# pi433_r02.net
KiCad netlist of a schematic drawn in EAGLE
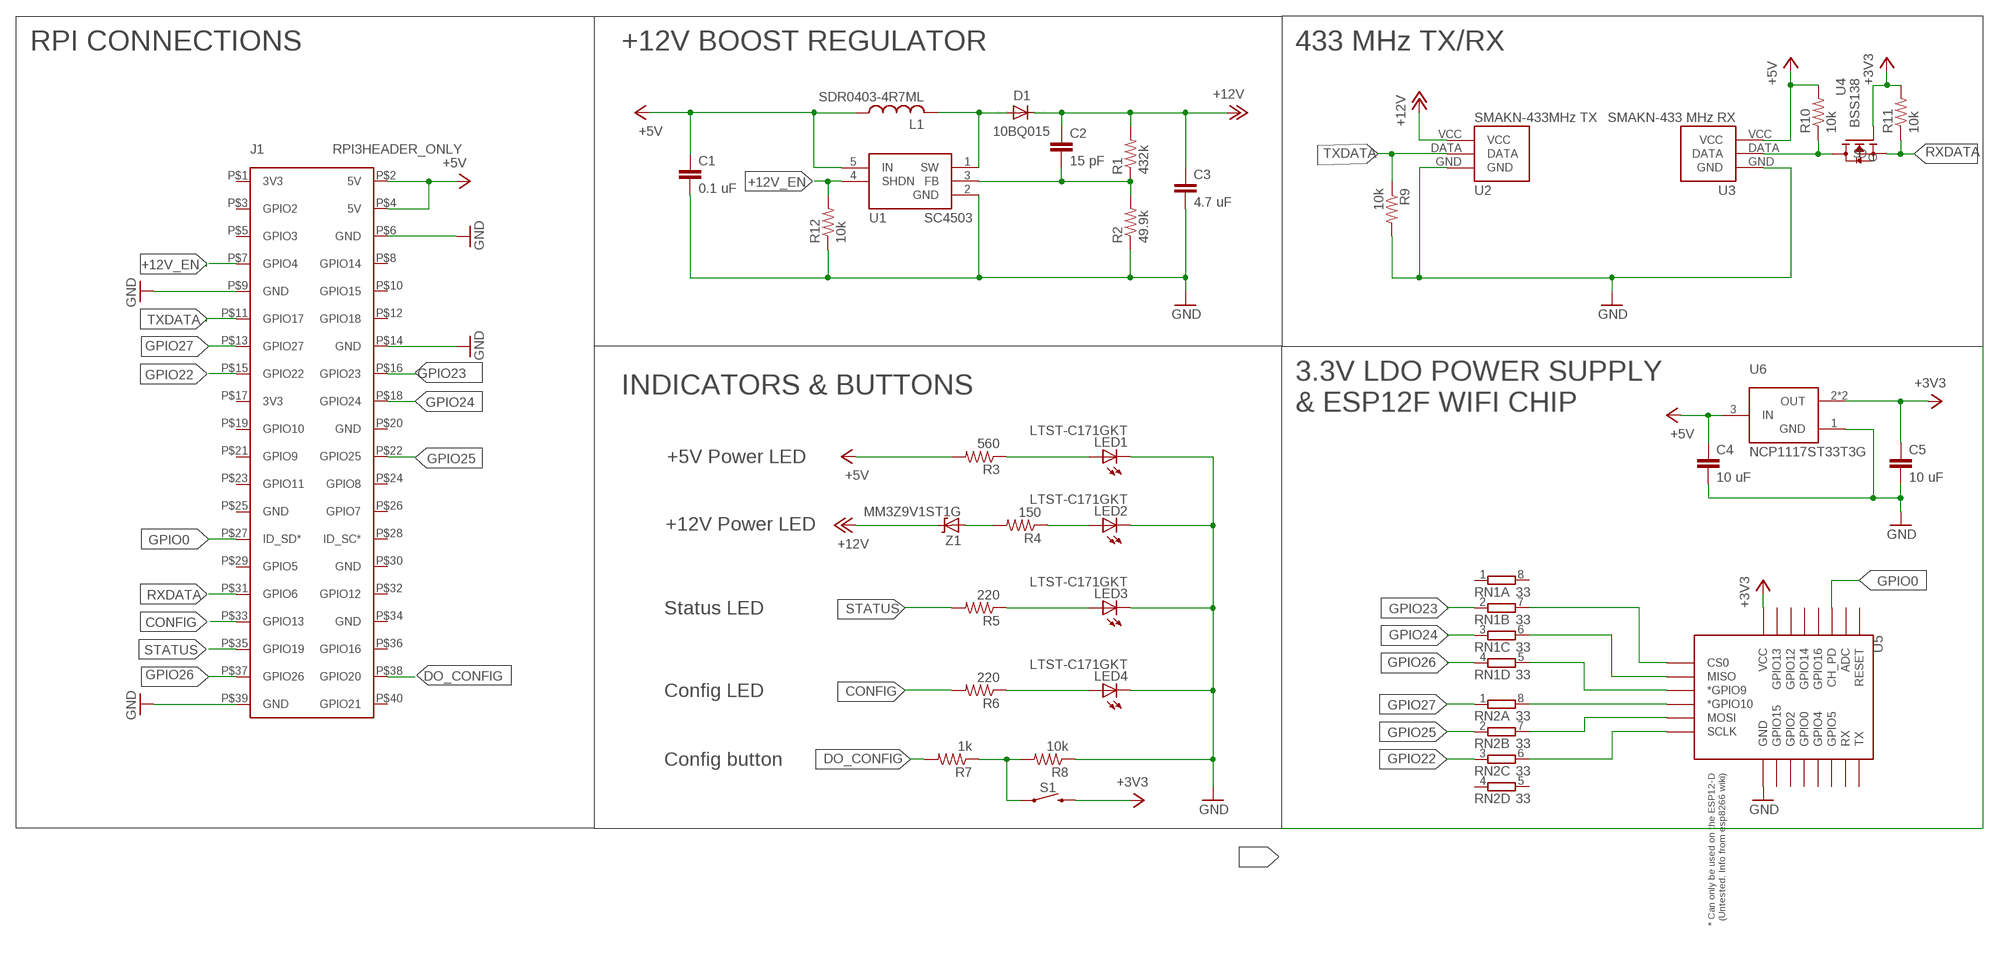
[diagram p0: schematic, sheet 1]

(export (version "E")
  (design (tool "Eeschema 10.0.6"))
  (components
    (comp (ref "C1")
      (value "0.1 uF")
      (footprint "eagle-import:C0603")
      (libsource (lib "eagle-import") (part "C-EUC0603"))
    )
    (comp (ref "C2")
      (value "15 pF")
      (footprint "eagle-import:C0603")
      (libsource (lib "eagle-import") (part "C-EUC0603"))
    )
    (comp (ref "C3")
      (value "4.7 uF")
      (footprint "eagle-import:C0805")
      (libsource (lib "eagle-import") (part "C-EUC0805"))
    )
    (comp (ref "C4")
      (value "10 uF")
      (footprint "eagle-import:C0805")
      (libsource (lib "eagle-import") (part "C-EUC0805"))
    )
    (comp (ref "C5")
      (value "10 uF")
      (footprint "eagle-import:C0805")
      (libsource (lib "eagle-import") (part "C-EUC0805"))
    )
    (comp (ref "D1")
      (value "10BQ015")
      (footprint "eagle-import:DO214AA")
      (libsource (lib "eagle-import") (part "DIODE-DO214AA"))
    )
    (comp (ref "J1")
      (value "RPI3HEADER_ONLY")
      (footprint "eagle-import:RPI3-HEADER_ONLY")
      (libsource (lib "eagle-import") (part "RPI3HEADER_ONLY"))
    )
    (comp (ref "L1")
      (value "SDR0403-4R7ML")
      (footprint "eagle-import:SDR0403")
      (libsource (lib "eagle-import") (part "SDR0403-4R7ML"))
    )
    (comp (ref "LED1")
      (value "LTST-C171GKT")
      (footprint "eagle-import:CHIPLED_0805")
      (libsource (lib "eagle-import") (part "LEDCHIPLED_0805"))
    )
    (comp (ref "LED2")
      (value "LTST-C171GKT")
      (footprint "eagle-import:CHIPLED_0805")
      (libsource (lib "eagle-import") (part "LEDCHIPLED_0805"))
    )
    (comp (ref "LED3")
      (value "LTST-C171GKT")
      (footprint "eagle-import:CHIPLED_0805")
      (libsource (lib "eagle-import") (part "LEDCHIPLED_0805"))
    )
    (comp (ref "LED4")
      (value "LTST-C171GKT")
      (footprint "eagle-import:CHIPLED_0805")
      (libsource (lib "eagle-import") (part "LEDCHIPLED_0805"))
    )
    (comp (ref "R1")
      (value "432k")
      (footprint "eagle-import:R0805")
      (libsource (lib "eagle-import") (part "R-US_R0805"))
    )
    (comp (ref "R2")
      (value "49.9k")
      (footprint "eagle-import:R0805")
      (libsource (lib "eagle-import") (part "R-US_R0805"))
    )
    (comp (ref "R3")
      (value "560")
      (footprint "eagle-import:R0805")
      (libsource (lib "eagle-import") (part "R-US_R0805"))
    )
    (comp (ref "R4")
      (value "150")
      (footprint "eagle-import:R0805")
      (libsource (lib "eagle-import") (part "R-US_R0805"))
    )
    (comp (ref "R5")
      (value "220")
      (footprint "eagle-import:R0805")
      (libsource (lib "eagle-import") (part "R-US_R0805"))
    )
    (comp (ref "R6")
      (value "220")
      (footprint "eagle-import:R0805")
      (libsource (lib "eagle-import") (part "R-US_R0805"))
    )
    (comp (ref "R7")
      (value "1k")
      (footprint "eagle-import:R0805")
      (libsource (lib "eagle-import") (part "R-US_R0805"))
    )
    (comp (ref "R8")
      (value "10k")
      (footprint "eagle-import:R0805")
      (libsource (lib "eagle-import") (part "R-US_R0805"))
    )
    (comp (ref "R9")
      (value "10k")
      (footprint "eagle-import:R0805")
      (libsource (lib "eagle-import") (part "R-US_R0805"))
    )
    (comp (ref "R10")
      (value "10k")
      (footprint "eagle-import:R0805")
      (libsource (lib "eagle-import") (part "R-US_R0805"))
    )
    (comp (ref "R11")
      (value "10k")
      (footprint "eagle-import:R0805")
      (libsource (lib "eagle-import") (part "R-US_R0805"))
    )
    (comp (ref "R12")
      (value "10k")
      (footprint "eagle-import:R0805")
      (libsource (lib "eagle-import") (part "R-US_R0805"))
    )
    (comp (ref "RN1")
      (value "33")
      (footprint "eagle-import:CAY16")
      (libsource (lib "eagle-import") (part "4R-NCAY16"))
    )
    (comp (ref "RN2")
      (value "33")
      (footprint "eagle-import:CAY16")
      (libsource (lib "eagle-import") (part "4R-NCAY16"))
    )
    (comp (ref "S1")
      (value "MOMENTARY-SWITCH-SPST-SMD-6.0X3.5MM")
      (footprint "eagle-import:TACTILE_SWITCH_SMD_6.0X3.5MM")
      (libsource (lib "eagle-import") (part "MOMENTARY-SWITCH-SPST-SMD-6.0X3.5MM"))
    )
    (comp (ref "U1")
      (value "SC4503")
      (footprint "eagle-import:TSOT-23-5")
      (libsource (lib "eagle-import") (part "SC4503"))
    )
    (comp (ref "U2")
      (value "SMAKN-433TX")
      (footprint "eagle-import:SMAKN-433TX")
      (libsource (lib "eagle-import") (part "SMAKN-433TX"))
    )
    (comp (ref "U3")
      (value "SMAKN-433RX")
      (footprint "eagle-import:SMAKN-433RX")
      (libsource (lib "eagle-import") (part "SMAKN-433RX"))
    )
    (comp (ref "U4")
      (value "BSS138")
      (footprint "eagle-import:BSS138")
      (fields (field (name "MF") "Fairchild Semiconductor"))
      (libsource (lib "eagle-import") (part "BSS138"))
    )
    (comp (ref "U5")
      (value "ESP12ESMD")
      (footprint "eagle-import:ESP12E-SMD")
      (libsource (lib "eagle-import") (part "ESP12ESMD"))
    )
    (comp (ref "U6")
      (value "NCP1117ST33T3G")
      (footprint "eagle-import:SOT230P700X180-4N")
      (fields (field (name "MF") "ON Semiconductor"))
      (libsource (lib "eagle-import") (part "NCP1117ST33T3G"))
    )
    (comp (ref "Z1")
      (value "MM3Z9V1ST1G")
      (footprint "eagle-import:ZENER-SOD323")
      (libsource (lib "eagle-import") (part "MM3Z9V1ST1G"))
    )
  )
  (nets
    (net (code "1") (name "+3V3") (class "Default")
      (node (ref "C5") (pin "1") (pinfunction "1_1") (pintype "passive"))
      (node (ref "R11") (pin "2") (pinfunction "2_2") (pintype "passive"))
      (node (ref "S1") (pin "2") (pinfunction "2_2") (pintype "passive"))
      (node (ref "U4") (pin "G") (pinfunction "G_G") (pintype "passive"))
      (node (ref "U5") (pin "VCC") (pinfunction "VCC_VCC") (pintype "bidirectional"))
      (node (ref "U6") (pin "2") (pinfunction "OUT_2") (pintype "output"))
      (node (ref "U6") (pin "4") (pinfunction "OUT_4") (pintype "output"))
    )
    (net (code "2") (name "+5V") (class "Default")
      (node (ref "C1") (pin "1") (pinfunction "1_1") (pintype "passive"))
      (node (ref "C4") (pin "1") (pinfunction "1_1") (pintype "passive"))
      (node (ref "J1") (pin "P$2") (pinfunction "5V_P$2") (pintype "bidirectional"))
      (node (ref "J1") (pin "P$4") (pinfunction "5V_P$4") (pintype "bidirectional"))
      (node (ref "L1") (pin "P$1") (pinfunction "1_P$1") (pintype "passive"))
      (node (ref "R10") (pin "2") (pinfunction "2_2") (pintype "passive"))
      (node (ref "R3") (pin "2") (pinfunction "2_2") (pintype "passive"))
      (node (ref "U1") (pin "5") (pinfunction "IN_5") (pintype "power_in"))
      (node (ref "U3") (pin "VCC") (pinfunction "VCC_VCC") (pintype "bidirectional"))
      (node (ref "U6") (pin "3") (pinfunction "IN_3") (pintype "input"))
    )
    (net (code "3") (name "+12V") (class "Default")
      (node (ref "C2") (pin "1") (pinfunction "1_1") (pintype "passive"))
      (node (ref "C3") (pin "1") (pinfunction "1_1") (pintype "passive"))
      (node (ref "D1") (pin "C") (pinfunction "C_C") (pintype "passive"))
      (node (ref "R1") (pin "2") (pinfunction "2_2") (pintype "passive"))
      (node (ref "U2") (pin "VCC") (pinfunction "VCC_VCC") (pintype "bidirectional"))
      (node (ref "Z1") (pin "C") (pinfunction "C_C") (pintype "passive"))
    )
    (net (code "4") (name "/+12V_EN") (class "Default")
      (node (ref "J1") (pin "P$7") (pinfunction "GPIO4_P$7") (pintype "bidirectional"))
      (node (ref "R12") (pin "2") (pinfunction "2_2") (pintype "passive"))
      (node (ref "U1") (pin "4") (pinfunction "SHDN_4") (pintype "input"))
    )
    (net (code "5") (name "/CONFIG") (class "Default")
      (node (ref "J1") (pin "P$33") (pinfunction "GPIO13_P$33") (pintype "bidirectional"))
      (node (ref "R6") (pin "2") (pinfunction "2_2") (pintype "passive"))
    )
    (net (code "6") (name "/DO_CONFIG") (class "Default")
      (node (ref "J1") (pin "P$38") (pinfunction "GPIO20_P$38") (pintype "bidirectional"))
      (node (ref "R7") (pin "2") (pinfunction "2_2") (pintype "passive"))
    )
    (net (code "7") (name "/GPIO0") (class "Default")
      (node (ref "J1") (pin "P$27") (pinfunction "ID_SD*_P$27") (pintype "bidirectional"))
      (node (ref "U5") (pin "CH_PD") (pinfunction "CH_PD_CH_PD") (pintype "bidirectional"))
    )
    (net (code "8") (name "/GPIO22") (class "Default")
      (node (ref "J1") (pin "P$15") (pinfunction "GPIO22_P$15") (pintype "bidirectional"))
      (node (ref "RN2") (pin "3") (pinfunction "1_3") (pintype "passive"))
    )
    (net (code "9") (name "/GPIO23") (class "Default")
      (node (ref "J1") (pin "P$16") (pinfunction "GPIO23_P$16") (pintype "bidirectional"))
      (node (ref "RN1") (pin "2") (pinfunction "1_2") (pintype "passive"))
    )
    (net (code "10") (name "/GPIO24") (class "Default")
      (node (ref "J1") (pin "P$18") (pinfunction "GPIO24_P$18") (pintype "bidirectional"))
      (node (ref "RN1") (pin "3") (pinfunction "1_3") (pintype "passive"))
    )
    (net (code "11") (name "/GPIO25") (class "Default")
      (node (ref "J1") (pin "P$22") (pinfunction "GPIO25_P$22") (pintype "bidirectional"))
      (node (ref "RN2") (pin "2") (pinfunction "1_2") (pintype "passive"))
    )
    (net (code "12") (name "/GPIO26") (class "Default")
      (node (ref "J1") (pin "P$37") (pinfunction "GPIO26_P$37") (pintype "bidirectional"))
      (node (ref "RN1") (pin "4") (pinfunction "1_4") (pintype "passive"))
    )
    (net (code "13") (name "/GPIO27") (class "Default")
      (node (ref "J1") (pin "P$13") (pinfunction "GPIO27_P$13") (pintype "bidirectional"))
      (node (ref "RN2") (pin "1") (pinfunction "1_1") (pintype "passive"))
    )
    (net (code "14") (name "/RXDATA") (class "Default")
      (node (ref "J1") (pin "P$31") (pinfunction "GPIO6_P$31") (pintype "bidirectional"))
      (node (ref "R11") (pin "1") (pinfunction "1_1") (pintype "passive"))
      (node (ref "U4") (pin "S") (pinfunction "S_S") (pintype "passive"))
    )
    (net (code "15") (name "/STATUS") (class "Default")
      (node (ref "J1") (pin "P$35") (pinfunction "GPIO19_P$35") (pintype "bidirectional"))
      (node (ref "R5") (pin "2") (pinfunction "2_2") (pintype "passive"))
    )
    (net (code "16") (name "/TXDATA") (class "Default")
      (node (ref "J1") (pin "P$11") (pinfunction "GPIO17_P$11") (pintype "bidirectional"))
      (node (ref "R9") (pin "1") (pinfunction "1_1") (pintype "passive"))
      (node (ref "U2") (pin "DATA") (pinfunction "DATA_DATA") (pintype "bidirectional"))
    )
    (net (code "17") (name "GND") (class "Default")
      (node (ref "C1") (pin "2") (pinfunction "2_2") (pintype "passive"))
      (node (ref "C3") (pin "2") (pinfunction "2_2") (pintype "passive"))
      (node (ref "C4") (pin "2") (pinfunction "2_2") (pintype "passive"))
      (node (ref "C5") (pin "2") (pinfunction "2_2") (pintype "passive"))
      (node (ref "J1") (pin "P$14") (pinfunction "GND_P$14") (pintype "bidirectional"))
      (node (ref "J1") (pin "P$39") (pinfunction "GND_P$39") (pintype "bidirectional"))
      (node (ref "J1") (pin "P$6") (pinfunction "GND_P$6") (pintype "bidirectional"))
      (node (ref "J1") (pin "P$9") (pinfunction "GND_P$9") (pintype "bidirectional"))
      (node (ref "LED1") (pin "C") (pinfunction "C_C") (pintype "passive"))
      (node (ref "LED2") (pin "C") (pinfunction "C_C") (pintype "passive"))
      (node (ref "LED3") (pin "C") (pinfunction "C_C") (pintype "passive"))
      (node (ref "LED4") (pin "C") (pinfunction "C_C") (pintype "passive"))
      (node (ref "R12") (pin "1") (pinfunction "1_1") (pintype "passive"))
      (node (ref "R2") (pin "1") (pinfunction "1_1") (pintype "passive"))
      (node (ref "R8") (pin "1") (pinfunction "1_1") (pintype "passive"))
      (node (ref "R9") (pin "2") (pinfunction "2_2") (pintype "passive"))
      (node (ref "U1") (pin "2") (pinfunction "GND_2") (pintype "input"))
      (node (ref "U2") (pin "GND") (pinfunction "GND_GND") (pintype "bidirectional"))
      (node (ref "U3") (pin "GND") (pinfunction "GND_GND") (pintype "bidirectional"))
      (node (ref "U5") (pin "GND") (pinfunction "GND_GND") (pintype "bidirectional"))
      (node (ref "U6") (pin "1") (pinfunction "GND_1") (pintype "power_in"))
    )
    (net (code "18") (name "Net-(L1-2)") (class "Default")
      (node (ref "D1") (pin "A") (pinfunction "A_A") (pintype "passive"))
      (node (ref "L1") (pin "P$2") (pinfunction "2_P$2") (pintype "passive"))
      (node (ref "U1") (pin "1") (pinfunction "SW_1") (pintype "input"))
    )
    (net (code "19") (name "Net-(LED1-PadA)") (class "Default")
      (node (ref "LED1") (pin "A") (pinfunction "A_A") (pintype "passive"))
      (node (ref "R3") (pin "1") (pinfunction "1_1") (pintype "passive"))
    )
    (net (code "20") (name "Net-(LED2-PadA)") (class "Default")
      (node (ref "LED2") (pin "A") (pinfunction "A_A") (pintype "passive"))
      (node (ref "R4") (pin "1") (pinfunction "1_1") (pintype "passive"))
    )
    (net (code "21") (name "Net-(LED3-PadA)") (class "Default")
      (node (ref "LED3") (pin "A") (pinfunction "A_A") (pintype "passive"))
      (node (ref "R5") (pin "1") (pinfunction "1_1") (pintype "passive"))
    )
    (net (code "22") (name "Net-(LED4-PadA)") (class "Default")
      (node (ref "LED4") (pin "A") (pinfunction "A_A") (pintype "passive"))
      (node (ref "R6") (pin "1") (pinfunction "1_1") (pintype "passive"))
    )
    (net (code "23") (name "Net-(R4-Pad2)") (class "Default")
      (node (ref "R4") (pin "2") (pinfunction "2_2") (pintype "passive"))
      (node (ref "Z1") (pin "A") (pinfunction "A_A") (pintype "passive"))
    )
    (net (code "24") (name "Net-(R7-Pad1)") (class "Default")
      (node (ref "R7") (pin "1") (pinfunction "1_1") (pintype "passive"))
      (node (ref "R8") (pin "2") (pinfunction "2_2") (pintype "passive"))
      (node (ref "S1") (pin "1") (pinfunction "1_1") (pintype "passive"))
    )
    (net (code "25") (name "Net-(R10-Pad1)") (class "Default")
      (node (ref "R10") (pin "1") (pinfunction "1_1") (pintype "passive"))
      (node (ref "U3") (pin "DATA") (pinfunction "DATA_DATA") (pintype "bidirectional"))
      (node (ref "U4") (pin "D") (pinfunction "D_D") (pintype "passive"))
    )
    (net (code "26") (name "Net-(RN1B-2)") (class "Default")
      (node (ref "RN1") (pin "7") (pinfunction "2_7") (pintype "passive"))
      (node (ref "U5") (pin "CS0") (pinfunction "CS0_CS0") (pintype "bidirectional"))
    )
    (net (code "27") (name "Net-(RN1C-2)") (class "Default")
      (node (ref "RN1") (pin "6") (pinfunction "2_6") (pintype "passive"))
      (node (ref "U5") (pin "MISO") (pinfunction "MISO_MISO") (pintype "bidirectional"))
    )
    (net (code "28") (name "Net-(RN1D-2)") (class "Default")
      (node (ref "RN1") (pin "5") (pinfunction "2_5") (pintype "passive"))
      (node (ref "U5") (pin "GPIO9") (pinfunction "*GPIO9_GPIO9") (pintype "bidirectional"))
    )
    (net (code "29") (name "Net-(RN2A-2)") (class "Default")
      (node (ref "RN2") (pin "8") (pinfunction "2_8") (pintype "passive"))
      (node (ref "U5") (pin "GPIO10") (pinfunction "*GPIO10_GPIO10") (pintype "bidirectional"))
    )
    (net (code "30") (name "Net-(RN2B-2)") (class "Default")
      (node (ref "RN2") (pin "7") (pinfunction "2_7") (pintype "passive"))
      (node (ref "U5") (pin "MOSI") (pinfunction "MOSI_MOSI") (pintype "bidirectional"))
    )
    (net (code "31") (name "Net-(RN2C-2)") (class "Default")
      (node (ref "RN2") (pin "6") (pinfunction "2_6") (pintype "passive"))
      (node (ref "U5") (pin "SCLK") (pinfunction "SCLK_SCLK") (pintype "bidirectional"))
    )
    (net (code "32") (name "Net-(U1-FB)") (class "Default")
      (node (ref "C2") (pin "2") (pinfunction "2_2") (pintype "passive"))
      (node (ref "R1") (pin "1") (pinfunction "1_1") (pintype "passive"))
      (node (ref "R2") (pin "2") (pinfunction "2_2") (pintype "passive"))
      (node (ref "U1") (pin "3") (pinfunction "FB_3") (pintype "input"))
    )
    (net (code "33") (name "unconnected-(J1-3V3-PadP$1)") (class "Default")
      (node (ref "J1") (pin "P$1") (pinfunction "3V3_P$1") (pintype "bidirectional"))
    )
    (net (code "34") (name "unconnected-(J1-3V3-PadP$17)") (class "Default")
      (node (ref "J1") (pin "P$17") (pinfunction "3V3_P$17") (pintype "bidirectional"))
    )
    (net (code "35") (name "unconnected-(J1-GND-PadP$20)") (class "Default")
      (node (ref "J1") (pin "P$20") (pinfunction "GND_P$20") (pintype "bidirectional"))
    )
    (net (code "36") (name "unconnected-(J1-GND-PadP$25)") (class "Default")
      (node (ref "J1") (pin "P$25") (pinfunction "GND_P$25") (pintype "bidirectional"))
    )
    (net (code "37") (name "unconnected-(J1-GND-PadP$30)") (class "Default")
      (node (ref "J1") (pin "P$30") (pinfunction "GND_P$30") (pintype "bidirectional"))
    )
    (net (code "38") (name "unconnected-(J1-GND-PadP$34)") (class "Default")
      (node (ref "J1") (pin "P$34") (pinfunction "GND_P$34") (pintype "bidirectional"))
    )
    (net (code "39") (name "unconnected-(J1-GPIO2-PadP$3)") (class "Default")
      (node (ref "J1") (pin "P$3") (pinfunction "GPIO2_P$3") (pintype "bidirectional"))
    )
    (net (code "40") (name "unconnected-(J1-GPIO3-PadP$5)") (class "Default")
      (node (ref "J1") (pin "P$5") (pinfunction "GPIO3_P$5") (pintype "bidirectional"))
    )
    (net (code "41") (name "unconnected-(J1-GPIO5-PadP$29)") (class "Default")
      (node (ref "J1") (pin "P$29") (pinfunction "GPIO5_P$29") (pintype "bidirectional"))
    )
    (net (code "42") (name "unconnected-(J1-GPIO7-PadP$26)") (class "Default")
      (node (ref "J1") (pin "P$26") (pinfunction "GPIO7_P$26") (pintype "bidirectional"))
    )
    (net (code "43") (name "unconnected-(J1-GPIO8-PadP$24)") (class "Default")
      (node (ref "J1") (pin "P$24") (pinfunction "GPIO8_P$24") (pintype "bidirectional"))
    )
    (net (code "44") (name "unconnected-(J1-GPIO9-PadP$21)") (class "Default")
      (node (ref "J1") (pin "P$21") (pinfunction "GPIO9_P$21") (pintype "bidirectional"))
    )
    (net (code "45") (name "unconnected-(J1-GPIO10-PadP$19)") (class "Default")
      (node (ref "J1") (pin "P$19") (pinfunction "GPIO10_P$19") (pintype "bidirectional"))
    )
    (net (code "46") (name "unconnected-(J1-GPIO11-PadP$23)") (class "Default")
      (node (ref "J1") (pin "P$23") (pinfunction "GPIO11_P$23") (pintype "bidirectional"))
    )
    (net (code "47") (name "unconnected-(J1-GPIO12-PadP$32)") (class "Default")
      (node (ref "J1") (pin "P$32") (pinfunction "GPIO12_P$32") (pintype "bidirectional"))
    )
    (net (code "48") (name "unconnected-(J1-GPIO14-PadP$8)") (class "Default")
      (node (ref "J1") (pin "P$8") (pinfunction "GPIO14_P$8") (pintype "bidirectional"))
    )
    (net (code "49") (name "unconnected-(J1-GPIO15-PadP$10)") (class "Default")
      (node (ref "J1") (pin "P$10") (pinfunction "GPIO15_P$10") (pintype "bidirectional"))
    )
    (net (code "50") (name "unconnected-(J1-GPIO16-PadP$36)") (class "Default")
      (node (ref "J1") (pin "P$36") (pinfunction "GPIO16_P$36") (pintype "bidirectional"))
    )
    (net (code "51") (name "unconnected-(J1-GPIO18-PadP$12)") (class "Default")
      (node (ref "J1") (pin "P$12") (pinfunction "GPIO18_P$12") (pintype "bidirectional"))
    )
    (net (code "52") (name "unconnected-(J1-GPIO21-PadP$40)") (class "Default")
      (node (ref "J1") (pin "P$40") (pinfunction "GPIO21_P$40") (pintype "bidirectional"))
    )
    (net (code "53") (name "unconnected-(J1-ID_SC*-PadP$28)") (class "Default")
      (node (ref "J1") (pin "P$28") (pinfunction "ID_SC*_P$28") (pintype "bidirectional"))
    )
    (net (code "54") (name "unconnected-(RN1-Pad1)") (class "Default")
      (node (ref "RN1") (pin "1") (pinfunction "1_1") (pintype "passive"))
    )
    (net (code "55") (name "unconnected-(RN1A-2-Pad8)") (class "Default")
      (node (ref "RN1") (pin "8") (pinfunction "2_8") (pintype "passive"))
    )
    (net (code "56") (name "unconnected-(RN2D-1-Pad4)") (class "Default")
      (node (ref "RN2") (pin "4") (pinfunction "1_4") (pintype "passive"))
    )
    (net (code "57") (name "unconnected-(RN2D-2-Pad5)") (class "Default")
      (node (ref "RN2") (pin "5") (pinfunction "2_5") (pintype "passive"))
    )
    (net (code "58") (name "unconnected-(U5-PadADC)") (class "Default")
      (node (ref "U5") (pin "ADC") (pinfunction "ADC_ADC") (pintype "bidirectional"))
    )
    (net (code "59") (name "unconnected-(U5-PadGPIO0)") (class "Default")
      (node (ref "U5") (pin "GPIO0") (pinfunction "GPIO0_GPIO0") (pintype "bidirectional"))
    )
    (net (code "60") (name "unconnected-(U5-PadGPIO2)") (class "Default")
      (node (ref "U5") (pin "GPIO2") (pinfunction "GPIO2_GPIO2") (pintype "bidirectional"))
    )
    (net (code "61") (name "unconnected-(U5-PadGPIO4)") (class "Default")
      (node (ref "U5") (pin "GPIO4") (pinfunction "GPIO4_GPIO4") (pintype "bidirectional"))
    )
    (net (code "62") (name "unconnected-(U5-PadGPIO5)") (class "Default")
      (node (ref "U5") (pin "GPIO5") (pinfunction "GPIO5_GPIO5") (pintype "bidirectional"))
    )
    (net (code "63") (name "unconnected-(U5-PadGPIO12)") (class "Default")
      (node (ref "U5") (pin "GPIO12") (pinfunction "GPIO12_GPIO12") (pintype "bidirectional"))
    )
    (net (code "64") (name "unconnected-(U5-PadGPIO13)") (class "Default")
      (node (ref "U5") (pin "GPIO13") (pinfunction "GPIO13_GPIO13") (pintype "bidirectional"))
    )
    (net (code "65") (name "unconnected-(U5-PadGPIO14)") (class "Default")
      (node (ref "U5") (pin "GPIO14") (pinfunction "GPIO14_GPIO14") (pintype "bidirectional"))
    )
    (net (code "66") (name "unconnected-(U5-PadGPIO15)") (class "Default")
      (node (ref "U5") (pin "GPIO15") (pinfunction "GPIO15_GPIO15") (pintype "bidirectional"))
    )
    (net (code "67") (name "unconnected-(U5-PadGPIO16)") (class "Default")
      (node (ref "U5") (pin "GPIO16") (pinfunction "GPIO16_GPIO16") (pintype "bidirectional"))
    )
    (net (code "68") (name "unconnected-(U5-PadRESET)") (class "Default")
      (node (ref "U5") (pin "RESET") (pinfunction "RESET_RESET") (pintype "bidirectional"))
    )
    (net (code "69") (name "unconnected-(U5-RX-PadRXD0)") (class "Default")
      (node (ref "U5") (pin "RXD0") (pinfunction "RX_RXD0") (pintype "bidirectional"))
    )
    (net (code "70") (name "unconnected-(U5-TX-PadTXD0)") (class "Default")
      (node (ref "U5") (pin "TXD0") (pinfunction "TX_TXD0") (pintype "bidirectional"))
    )
  )
)
